# flex_v1.net
KiCad netlist of a schematic drawn in EAGLE
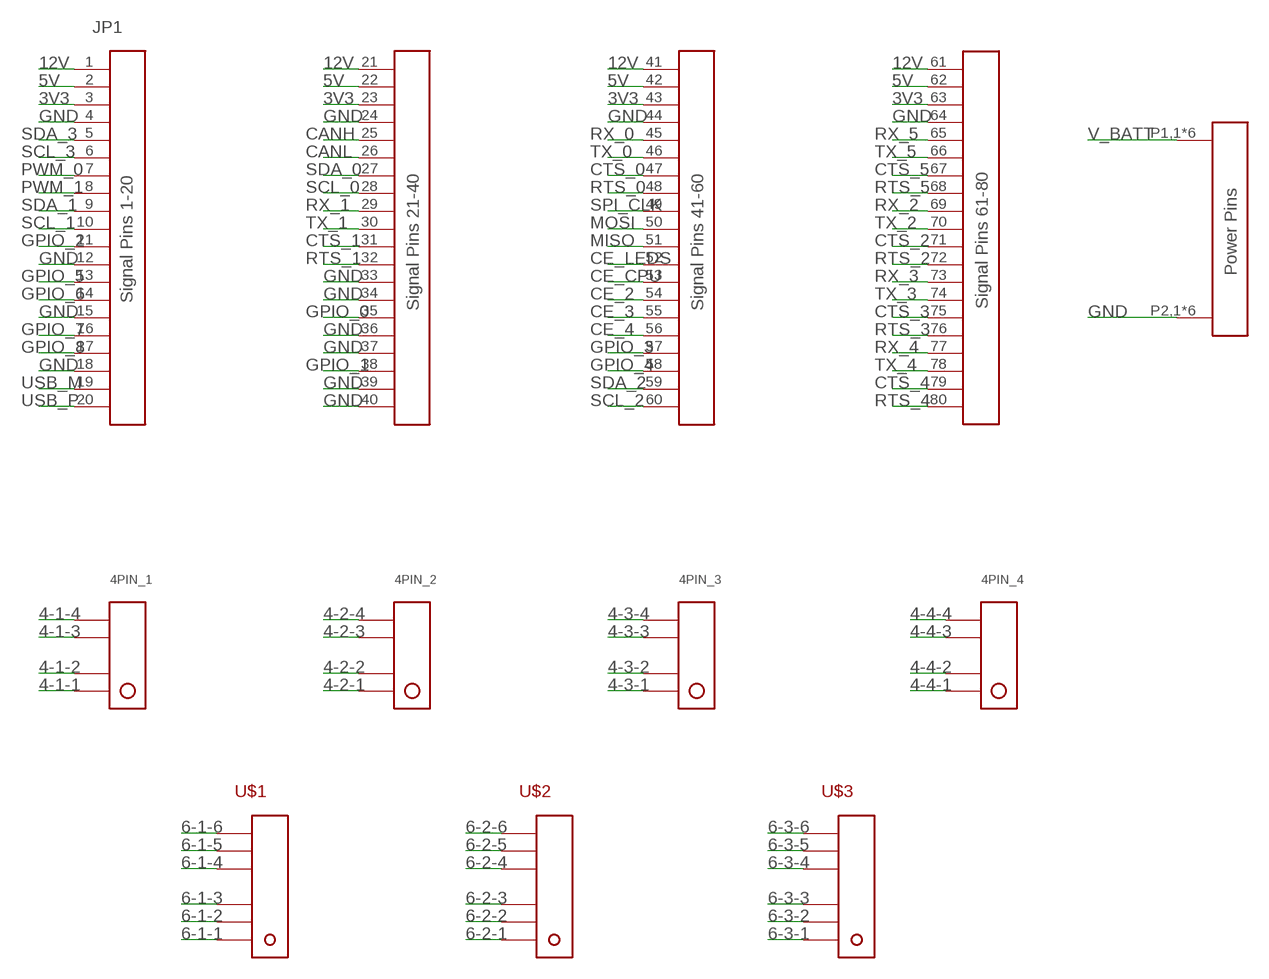
[diagram p0: schematic, sheet 1]

(export (version "E")
  (design (tool "Eeschema 10.0.6"))
  (components
    (comp (ref "4PIN_1")
      (value "KK254_VERT_4PIN22-29-2041")
      (footprint "eagle-import:KK254_VERT_4PIN")
      (libsource (lib "eagle-import") (part "KK254_VERT_4PIN22-29-2041"))
    )
    (comp (ref "4PIN_2")
      (value "KK254_VERT_4PIN22-29-2041")
      (footprint "eagle-import:KK254_VERT_4PIN")
      (libsource (lib "eagle-import") (part "KK254_VERT_4PIN22-29-2041"))
    )
    (comp (ref "4PIN_3")
      (value "KK254_VERT_4PIN22-29-2041")
      (footprint "eagle-import:KK254_VERT_4PIN")
      (libsource (lib "eagle-import") (part "KK254_VERT_4PIN22-29-2041"))
    )
    (comp (ref "4PIN_4")
      (value "KK254_VERT_4PIN22-29-2041")
      (footprint "eagle-import:KK254_VERT_4PIN")
      (libsource (lib "eagle-import") (part "KK254_VERT_4PIN22-29-2041"))
    )
    (comp (ref "JP1")
      (value "MPSC-01-80MPSC-RA-LC")
      (footprint "eagle-import:MPSC-01-80")
      (libsource (lib "eagle-import") (part "MPSC-01-80MPSC-RA-LC"))
    )
    (comp (ref "U$1")
      (value "KK254_6PIN")
      (footprint "eagle-import:KK254_6PIN")
      (libsource (lib "eagle-import") (part "KK254_6PIN"))
    )
    (comp (ref "U$2")
      (value "KK254_6PIN")
      (footprint "eagle-import:KK254_6PIN")
      (libsource (lib "eagle-import") (part "KK254_6PIN"))
    )
    (comp (ref "U$3")
      (value "KK254_6PIN")
      (footprint "eagle-import:KK254_6PIN")
      (libsource (lib "eagle-import") (part "KK254_6PIN"))
    )
  )
  (nets
    (net (code "1") (name "/3V3") (class "Default")
      (node (ref "JP1") (pin "23") (pinfunction "P$23_23") (pintype "bidirectional"))
      (node (ref "JP1") (pin "3") (pinfunction "P$3_3") (pintype "bidirectional"))
      (node (ref "JP1") (pin "43") (pinfunction "P$43_43") (pintype "bidirectional"))
      (node (ref "JP1") (pin "63") (pinfunction "P$63_63") (pintype "bidirectional"))
    )
    (net (code "2") (name "/4-1-1") (class "Default")
      (node (ref "4PIN_1") (pin "P$1") (pinfunction "P$1_P$1") (pintype "bidirectional"))
    )
    (net (code "3") (name "/4-1-2") (class "Default")
      (node (ref "4PIN_1") (pin "P$2") (pinfunction "P$2_P$2") (pintype "bidirectional"))
    )
    (net (code "4") (name "/4-1-3") (class "Default")
      (node (ref "4PIN_1") (pin "P$3") (pinfunction "P$3_P$3") (pintype "bidirectional"))
    )
    (net (code "5") (name "/4-1-4") (class "Default")
      (node (ref "4PIN_1") (pin "P$4") (pinfunction "P$4_P$4") (pintype "bidirectional"))
    )
    (net (code "6") (name "/4-2-1") (class "Default")
      (node (ref "4PIN_2") (pin "P$1") (pinfunction "P$1_P$1") (pintype "bidirectional"))
    )
    (net (code "7") (name "/4-2-2") (class "Default")
      (node (ref "4PIN_2") (pin "P$2") (pinfunction "P$2_P$2") (pintype "bidirectional"))
    )
    (net (code "8") (name "/4-2-3") (class "Default")
      (node (ref "4PIN_2") (pin "P$3") (pinfunction "P$3_P$3") (pintype "bidirectional"))
    )
    (net (code "9") (name "/4-2-4") (class "Default")
      (node (ref "4PIN_2") (pin "P$4") (pinfunction "P$4_P$4") (pintype "bidirectional"))
    )
    (net (code "10") (name "/4-3-1") (class "Default")
      (node (ref "4PIN_3") (pin "P$1") (pinfunction "P$1_P$1") (pintype "bidirectional"))
    )
    (net (code "11") (name "/4-3-2") (class "Default")
      (node (ref "4PIN_3") (pin "P$2") (pinfunction "P$2_P$2") (pintype "bidirectional"))
    )
    (net (code "12") (name "/4-3-3") (class "Default")
      (node (ref "4PIN_3") (pin "P$3") (pinfunction "P$3_P$3") (pintype "bidirectional"))
    )
    (net (code "13") (name "/4-3-4") (class "Default")
      (node (ref "4PIN_3") (pin "P$4") (pinfunction "P$4_P$4") (pintype "bidirectional"))
    )
    (net (code "14") (name "/4-4-1") (class "Default")
      (node (ref "4PIN_4") (pin "P$1") (pinfunction "P$1_P$1") (pintype "bidirectional"))
    )
    (net (code "15") (name "/4-4-2") (class "Default")
      (node (ref "4PIN_4") (pin "P$2") (pinfunction "P$2_P$2") (pintype "bidirectional"))
    )
    (net (code "16") (name "/4-4-3") (class "Default")
      (node (ref "4PIN_4") (pin "P$3") (pinfunction "P$3_P$3") (pintype "bidirectional"))
    )
    (net (code "17") (name "/4-4-4") (class "Default")
      (node (ref "4PIN_4") (pin "P$4") (pinfunction "P$4_P$4") (pintype "bidirectional"))
    )
    (net (code "18") (name "/5V") (class "Default")
      (node (ref "JP1") (pin "2") (pinfunction "P$2_2") (pintype "bidirectional"))
      (node (ref "JP1") (pin "22") (pinfunction "P$22_22") (pintype "bidirectional"))
      (node (ref "JP1") (pin "42") (pinfunction "P$42_42") (pintype "bidirectional"))
      (node (ref "JP1") (pin "62") (pinfunction "P$62_62") (pintype "bidirectional"))
    )
    (net (code "19") (name "/6-1-1") (class "Default")
      (node (ref "U$1") (pin "P$1") (pinfunction "P$1_P$1") (pintype "bidirectional"))
    )
    (net (code "20") (name "/6-1-2") (class "Default")
      (node (ref "U$1") (pin "P$2") (pinfunction "P$2_P$2") (pintype "bidirectional"))
    )
    (net (code "21") (name "/6-1-3") (class "Default")
      (node (ref "U$1") (pin "P$3") (pinfunction "P$3_P$3") (pintype "bidirectional"))
    )
    (net (code "22") (name "/6-1-4") (class "Default")
      (node (ref "U$1") (pin "P$4") (pinfunction "P$4_P$4") (pintype "bidirectional"))
    )
    (net (code "23") (name "/6-1-5") (class "Default")
      (node (ref "U$1") (pin "P$5") (pinfunction "P$5_P$5") (pintype "bidirectional"))
    )
    (net (code "24") (name "/6-1-6") (class "Default")
      (node (ref "U$1") (pin "P$6") (pinfunction "P$6_P$6") (pintype "bidirectional"))
    )
    (net (code "25") (name "/6-2-1") (class "Default")
      (node (ref "U$2") (pin "P$1") (pinfunction "P$1_P$1") (pintype "bidirectional"))
    )
    (net (code "26") (name "/6-2-2") (class "Default")
      (node (ref "U$2") (pin "P$2") (pinfunction "P$2_P$2") (pintype "bidirectional"))
    )
    (net (code "27") (name "/6-2-3") (class "Default")
      (node (ref "U$2") (pin "P$3") (pinfunction "P$3_P$3") (pintype "bidirectional"))
    )
    (net (code "28") (name "/6-2-4") (class "Default")
      (node (ref "U$2") (pin "P$4") (pinfunction "P$4_P$4") (pintype "bidirectional"))
    )
    (net (code "29") (name "/6-2-5") (class "Default")
      (node (ref "U$2") (pin "P$5") (pinfunction "P$5_P$5") (pintype "bidirectional"))
    )
    (net (code "30") (name "/6-2-6") (class "Default")
      (node (ref "U$2") (pin "P$6") (pinfunction "P$6_P$6") (pintype "bidirectional"))
    )
    (net (code "31") (name "/6-3-1") (class "Default")
      (node (ref "U$3") (pin "P$1") (pinfunction "P$1_P$1") (pintype "bidirectional"))
    )
    (net (code "32") (name "/6-3-2") (class "Default")
      (node (ref "U$3") (pin "P$2") (pinfunction "P$2_P$2") (pintype "bidirectional"))
    )
    (net (code "33") (name "/6-3-3") (class "Default")
      (node (ref "U$3") (pin "P$3") (pinfunction "P$3_P$3") (pintype "bidirectional"))
    )
    (net (code "34") (name "/6-3-4") (class "Default")
      (node (ref "U$3") (pin "P$4") (pinfunction "P$4_P$4") (pintype "bidirectional"))
    )
    (net (code "35") (name "/6-3-5") (class "Default")
      (node (ref "U$3") (pin "P$5") (pinfunction "P$5_P$5") (pintype "bidirectional"))
    )
    (net (code "36") (name "/6-3-6") (class "Default")
      (node (ref "U$3") (pin "P$6") (pinfunction "P$6_P$6") (pintype "bidirectional"))
    )
    (net (code "37") (name "/12V") (class "Default")
      (node (ref "JP1") (pin "1") (pinfunction "P$1_1") (pintype "bidirectional"))
      (node (ref "JP1") (pin "21") (pinfunction "P$21_21") (pintype "bidirectional"))
      (node (ref "JP1") (pin "41") (pinfunction "P$41_41") (pintype "bidirectional"))
      (node (ref "JP1") (pin "61") (pinfunction "P$61_61") (pintype "bidirectional"))
    )
    (net (code "38") (name "/CANH") (class "Default")
      (node (ref "JP1") (pin "25") (pinfunction "P$25_25") (pintype "bidirectional"))
    )
    (net (code "39") (name "/CANL") (class "Default")
      (node (ref "JP1") (pin "26") (pinfunction "P$26_26") (pintype "bidirectional"))
    )
    (net (code "40") (name "/CE_2") (class "Default")
      (node (ref "JP1") (pin "54") (pinfunction "P$54_54") (pintype "bidirectional"))
    )
    (net (code "41") (name "/CE_3") (class "Default")
      (node (ref "JP1") (pin "55") (pinfunction "P$55_55") (pintype "bidirectional"))
    )
    (net (code "42") (name "/CE_4") (class "Default")
      (node (ref "JP1") (pin "56") (pinfunction "P$56_56") (pintype "bidirectional"))
    )
    (net (code "43") (name "/CE_CPU") (class "Default")
      (node (ref "JP1") (pin "53") (pinfunction "P$53_53") (pintype "bidirectional"))
    )
    (net (code "44") (name "/CE_LEDS") (class "Default")
      (node (ref "JP1") (pin "52") (pinfunction "P$52_52") (pintype "bidirectional"))
    )
    (net (code "45") (name "/CTS_0") (class "Default")
      (node (ref "JP1") (pin "47") (pinfunction "P$47_47") (pintype "bidirectional"))
    )
    (net (code "46") (name "/CTS_1") (class "Default")
      (node (ref "JP1") (pin "31") (pinfunction "P$31_31") (pintype "bidirectional"))
    )
    (net (code "47") (name "/CTS_2") (class "Default")
      (node (ref "JP1") (pin "71") (pinfunction "P$71_71") (pintype "bidirectional"))
    )
    (net (code "48") (name "/CTS_3") (class "Default")
      (node (ref "JP1") (pin "75") (pinfunction "P$75_75") (pintype "bidirectional"))
    )
    (net (code "49") (name "/CTS_4") (class "Default")
      (node (ref "JP1") (pin "79") (pinfunction "P$79_79") (pintype "bidirectional"))
    )
    (net (code "50") (name "/CTS_5") (class "Default")
      (node (ref "JP1") (pin "67") (pinfunction "P$67_67") (pintype "bidirectional"))
    )
    (net (code "51") (name "/GND") (class "Default")
      (node (ref "JP1") (pin "12") (pinfunction "P$12_12") (pintype "bidirectional"))
      (node (ref "JP1") (pin "15") (pinfunction "P$15_15") (pintype "bidirectional"))
      (node (ref "JP1") (pin "18") (pinfunction "P$18_18") (pintype "bidirectional"))
      (node (ref "JP1") (pin "24") (pinfunction "P$24_24") (pintype "bidirectional"))
      (node (ref "JP1") (pin "33") (pinfunction "P$33_33") (pintype "bidirectional"))
      (node (ref "JP1") (pin "34") (pinfunction "P$34_34") (pintype "bidirectional"))
      (node (ref "JP1") (pin "36") (pinfunction "P$36_36") (pintype "bidirectional"))
      (node (ref "JP1") (pin "37") (pinfunction "P$37_37") (pintype "bidirectional"))
      (node (ref "JP1") (pin "39") (pinfunction "P$39_39") (pintype "bidirectional"))
      (node (ref "JP1") (pin "4") (pinfunction "P$4_4") (pintype "bidirectional"))
      (node (ref "JP1") (pin "40") (pinfunction "P$40_40") (pintype "bidirectional"))
      (node (ref "JP1") (pin "44") (pinfunction "P$44_44") (pintype "bidirectional"))
      (node (ref "JP1") (pin "64") (pinfunction "P$64_64") (pintype "bidirectional"))
      (node (ref "JP1") (pin "P2,1") (pinfunction "POWER2_P2,1") (pintype "bidirectional"))
      (node (ref "JP1") (pin "P2,2") (pinfunction "POWER2_P2,2") (pintype "bidirectional"))
      (node (ref "JP1") (pin "P2,3") (pinfunction "POWER2_P2,3") (pintype "bidirectional"))
      (node (ref "JP1") (pin "P2,4") (pinfunction "POWER2_P2,4") (pintype "bidirectional"))
      (node (ref "JP1") (pin "P2,5") (pinfunction "POWER2_P2,5") (pintype "bidirectional"))
      (node (ref "JP1") (pin "P2,6") (pinfunction "POWER2_P2,6") (pintype "bidirectional"))
    )
    (net (code "52") (name "/GPIO_0") (class "Default")
      (node (ref "JP1") (pin "35") (pinfunction "P$35_35") (pintype "bidirectional"))
    )
    (net (code "53") (name "/GPIO_1") (class "Default")
      (node (ref "JP1") (pin "38") (pinfunction "P$38_38") (pintype "bidirectional"))
    )
    (net (code "54") (name "/GPIO_2") (class "Default")
      (node (ref "JP1") (pin "11") (pinfunction "P$11_11") (pintype "bidirectional"))
    )
    (net (code "55") (name "/GPIO_3") (class "Default")
      (node (ref "JP1") (pin "57") (pinfunction "P$57_57") (pintype "bidirectional"))
    )
    (net (code "56") (name "/GPIO_4") (class "Default")
      (node (ref "JP1") (pin "58") (pinfunction "P$58_58") (pintype "bidirectional"))
    )
    (net (code "57") (name "/GPIO_5") (class "Default")
      (node (ref "JP1") (pin "13") (pinfunction "P$13_13") (pintype "bidirectional"))
    )
    (net (code "58") (name "/GPIO_6") (class "Default")
      (node (ref "JP1") (pin "14") (pinfunction "P$14_14") (pintype "bidirectional"))
    )
    (net (code "59") (name "/GPIO_7") (class "Default")
      (node (ref "JP1") (pin "16") (pinfunction "P$16_16") (pintype "bidirectional"))
    )
    (net (code "60") (name "/GPIO_8") (class "Default")
      (node (ref "JP1") (pin "17") (pinfunction "P$17_17") (pintype "bidirectional"))
    )
    (net (code "61") (name "/MISO") (class "Default")
      (node (ref "JP1") (pin "51") (pinfunction "P$51_51") (pintype "bidirectional"))
    )
    (net (code "62") (name "/MOSI") (class "Default")
      (node (ref "JP1") (pin "50") (pinfunction "P$50_50") (pintype "bidirectional"))
    )
    (net (code "63") (name "/PWM_0") (class "Default")
      (node (ref "JP1") (pin "7") (pinfunction "P$7_7") (pintype "bidirectional"))
    )
    (net (code "64") (name "/PWM_1") (class "Default")
      (node (ref "JP1") (pin "8") (pinfunction "P$8_8") (pintype "bidirectional"))
    )
    (net (code "65") (name "/RTS_0") (class "Default")
      (node (ref "JP1") (pin "48") (pinfunction "P$48_48") (pintype "bidirectional"))
    )
    (net (code "66") (name "/RTS_1") (class "Default")
      (node (ref "JP1") (pin "32") (pinfunction "P$32_32") (pintype "bidirectional"))
    )
    (net (code "67") (name "/RTS_2") (class "Default")
      (node (ref "JP1") (pin "72") (pinfunction "P$72_72") (pintype "bidirectional"))
    )
    (net (code "68") (name "/RTS_3") (class "Default")
      (node (ref "JP1") (pin "76") (pinfunction "P$76_76") (pintype "bidirectional"))
    )
    (net (code "69") (name "/RTS_4") (class "Default")
      (node (ref "JP1") (pin "80") (pinfunction "P$80_80") (pintype "bidirectional"))
    )
    (net (code "70") (name "/RTS_5") (class "Default")
      (node (ref "JP1") (pin "68") (pinfunction "P$68_68") (pintype "bidirectional"))
    )
    (net (code "71") (name "/RX_0") (class "Default")
      (node (ref "JP1") (pin "45") (pinfunction "P$45_45") (pintype "bidirectional"))
    )
    (net (code "72") (name "/RX_1") (class "Default")
      (node (ref "JP1") (pin "29") (pinfunction "P$29_29") (pintype "bidirectional"))
    )
    (net (code "73") (name "/RX_2") (class "Default")
      (node (ref "JP1") (pin "69") (pinfunction "P$69_69") (pintype "bidirectional"))
    )
    (net (code "74") (name "/RX_3") (class "Default")
      (node (ref "JP1") (pin "73") (pinfunction "P$73_73") (pintype "bidirectional"))
    )
    (net (code "75") (name "/RX_4") (class "Default")
      (node (ref "JP1") (pin "77") (pinfunction "P$77_77") (pintype "bidirectional"))
    )
    (net (code "76") (name "/RX_5") (class "Default")
      (node (ref "JP1") (pin "65") (pinfunction "P$65_65") (pintype "bidirectional"))
    )
    (net (code "77") (name "/SCL_0") (class "Default")
      (node (ref "JP1") (pin "28") (pinfunction "P$28_28") (pintype "bidirectional"))
    )
    (net (code "78") (name "/SCL_1") (class "Default")
      (node (ref "JP1") (pin "10") (pinfunction "P$10_10") (pintype "bidirectional"))
    )
    (net (code "79") (name "/SCL_2") (class "Default")
      (node (ref "JP1") (pin "60") (pinfunction "P$60_60") (pintype "bidirectional"))
    )
    (net (code "80") (name "/SCL_3") (class "Default")
      (node (ref "JP1") (pin "6") (pinfunction "P$6_6") (pintype "bidirectional"))
    )
    (net (code "81") (name "/SDA_0") (class "Default")
      (node (ref "JP1") (pin "27") (pinfunction "P$27_27") (pintype "bidirectional"))
    )
    (net (code "82") (name "/SDA_1") (class "Default")
      (node (ref "JP1") (pin "9") (pinfunction "P$9_9") (pintype "bidirectional"))
    )
    (net (code "83") (name "/SDA_2") (class "Default")
      (node (ref "JP1") (pin "59") (pinfunction "P$59_59") (pintype "bidirectional"))
    )
    (net (code "84") (name "/SDA_3") (class "Default")
      (node (ref "JP1") (pin "5") (pinfunction "P$5_5") (pintype "bidirectional"))
    )
    (net (code "85") (name "/SPI_CLK") (class "Default")
      (node (ref "JP1") (pin "49") (pinfunction "P$49_49") (pintype "bidirectional"))
    )
    (net (code "86") (name "/TX_0") (class "Default")
      (node (ref "JP1") (pin "46") (pinfunction "P$46_46") (pintype "bidirectional"))
    )
    (net (code "87") (name "/TX_1") (class "Default")
      (node (ref "JP1") (pin "30") (pinfunction "P$30_30") (pintype "bidirectional"))
    )
    (net (code "88") (name "/TX_2") (class "Default")
      (node (ref "JP1") (pin "70") (pinfunction "P$70_70") (pintype "bidirectional"))
    )
    (net (code "89") (name "/TX_3") (class "Default")
      (node (ref "JP1") (pin "74") (pinfunction "P$74_74") (pintype "bidirectional"))
    )
    (net (code "90") (name "/TX_4") (class "Default")
      (node (ref "JP1") (pin "78") (pinfunction "P$78_78") (pintype "bidirectional"))
    )
    (net (code "91") (name "/TX_5") (class "Default")
      (node (ref "JP1") (pin "66") (pinfunction "P$66_66") (pintype "bidirectional"))
    )
    (net (code "92") (name "/USB_M") (class "Default")
      (node (ref "JP1") (pin "19") (pinfunction "P$19_19") (pintype "bidirectional"))
    )
    (net (code "93") (name "/USB_P") (class "Default")
      (node (ref "JP1") (pin "20") (pinfunction "P$20_20") (pintype "bidirectional"))
    )
    (net (code "94") (name "/V_BATT") (class "Default")
      (node (ref "JP1") (pin "P1,1") (pinfunction "POWER1_P1,1") (pintype "bidirectional"))
      (node (ref "JP1") (pin "P1,2") (pinfunction "POWER1_P1,2") (pintype "bidirectional"))
      (node (ref "JP1") (pin "P1,3") (pinfunction "POWER1_P1,3") (pintype "bidirectional"))
      (node (ref "JP1") (pin "P1,4") (pinfunction "POWER1_P1,4") (pintype "bidirectional"))
      (node (ref "JP1") (pin "P1,5") (pinfunction "POWER1_P1,5") (pintype "bidirectional"))
      (node (ref "JP1") (pin "P1,6") (pinfunction "POWER1_P1,6") (pintype "bidirectional"))
    )
  )
)
